# Grove_-_3-Axis_Digital_Accelerometer_1_5.net
KiCad netlist of a schematic drawn in EAGLE
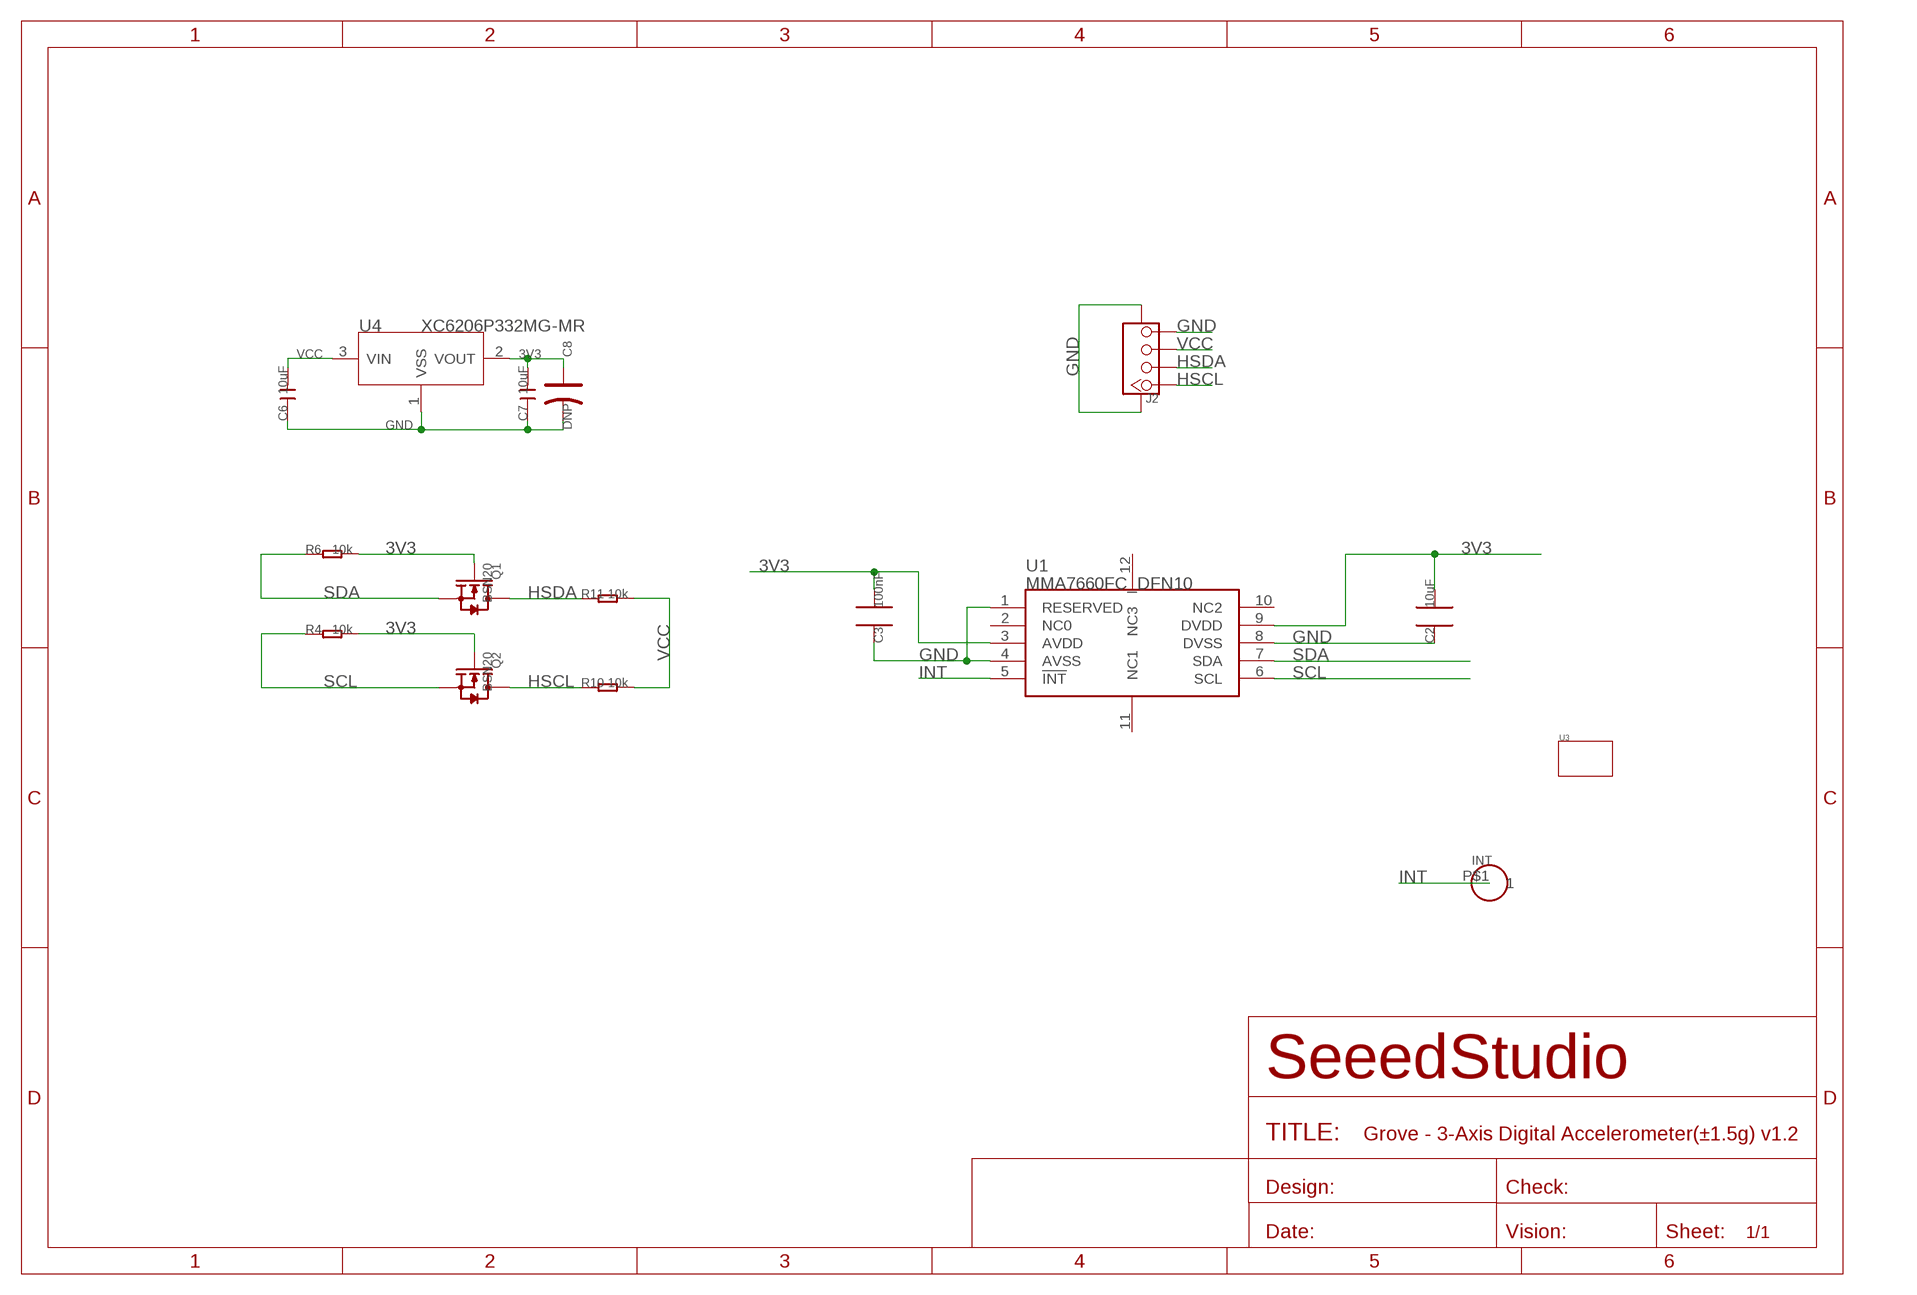
[diagram p0: schematic, sheet 1]

(export (version "E")
  (design (tool "Eeschema 10.0.6"))
  (components
    (comp (ref "C2")
      (value "10uF")
      (footprint "eagle-import:0805_S")
      (libsource (lib "eagle-import") (part "C0805_S"))
    )
    (comp (ref "C3")
      (value "100nF")
      (footprint "eagle-import:0603_S")
      (libsource (lib "eagle-import") (part "C0603_S"))
    )
    (comp (ref "C6")
      (value "10uF")
      (footprint "eagle-import:C0805")
      (libsource (lib "eagle-import") (part "C-0805"))
    )
    (comp (ref "C7")
      (value "10uF")
      (footprint "eagle-import:C0805")
      (libsource (lib "eagle-import") (part "C-0805"))
    )
    (comp (ref "C8")
      (value "DNP")
      (footprint "eagle-import:AVX-A")
      (libsource (lib "eagle-import") (part "CAP-AVX-A"))
    )
    (comp (ref "INT")
      (value "HEADER-1P-35")
      (footprint "eagle-import:1P-65_35MIL")
      (libsource (lib "eagle-import") (part "HEADER-1P-35"))
    )
    (comp (ref "J2")
      (value "TWIG-4P-2.0-SMD-FEMALE-REINFORCE'DD'")
      (footprint "eagle-import:4P-SMD-2.0")
      (libsource (lib "eagle-import") (part "TWIG-4P-2.0-SMD-FEMALE-REINFORCE'DD'"))
    )
    (comp (ref "Q1")
      (value "BSN20")
      (footprint "eagle-import:SOT23")
      (libsource (lib "eagle-import") (part "MOSFET-N'SOT23'"))
    )
    (comp (ref "Q2")
      (value "BSN20")
      (footprint "eagle-import:SOT23")
      (libsource (lib "eagle-import") (part "MOSFET-N'SOT23'"))
    )
    (comp (ref "R4")
      (value "10k")
      (footprint "eagle-import:R0603")
      (libsource (lib "eagle-import") (part "R-0603"))
    )
    (comp (ref "R6")
      (value "10k")
      (footprint "eagle-import:R0603")
      (libsource (lib "eagle-import") (part "R-0603"))
    )
    (comp (ref "R10")
      (value "10k")
      (footprint "eagle-import:R0603")
      (libsource (lib "eagle-import") (part "R-0603"))
    )
    (comp (ref "R11")
      (value "10k")
      (footprint "eagle-import:R0603")
      (libsource (lib "eagle-import") (part "R-0603"))
    )
    (comp (ref "U1")
      (value "MMA7660FC_DFN10")
      (footprint "eagle-import:DFN10")
      (libsource (lib "eagle-import") (part "MMA7660FC_DFN10"))
    )
    (comp (ref "U3")
      (value "TWIG-1U")
      (footprint "eagle-import:1U-DIM-W_-DRILL")
      (libsource (lib "eagle-import") (part "TWIG-1U"))
    )
    (comp (ref "U4")
      (value "XC6206P332MG-MR")
      (footprint "eagle-import:SOT23")
      (libsource (lib "eagle-import") (part "XC6206MR"))
    )
  )
  (nets
    (net (code "1") (name "/3V3") (class "Default")
      (node (ref "C2") (pin "2") (pinfunction "2_2") (pintype "bidirectional"))
      (node (ref "C3") (pin "2") (pinfunction "2_2") (pintype "bidirectional"))
      (node (ref "C7") (pin "2") (pinfunction "2_2") (pintype "passive"))
      (node (ref "C8") (pin "+") (pinfunction "+_+") (pintype "passive"))
      (node (ref "Q1") (pin "1") (pinfunction "G_1") (pintype "passive"))
      (node (ref "Q2") (pin "1") (pinfunction "G_1") (pintype "passive"))
      (node (ref "R4") (pin "2") (pinfunction "2_2") (pintype "passive"))
      (node (ref "R6") (pin "2") (pinfunction "2_2") (pintype "passive"))
      (node (ref "U1") (pin "3") (pinfunction "AVDD_3") (pintype "bidirectional"))
      (node (ref "U1") (pin "9") (pinfunction "DVDD_9") (pintype "bidirectional"))
      (node (ref "U4") (pin "2") (pinfunction "VOUT_2") (pintype "output"))
    )
    (net (code "2") (name "/GND") (class "Default")
      (node (ref "C2") (pin "1") (pinfunction "1_1") (pintype "bidirectional"))
      (node (ref "C3") (pin "1") (pinfunction "1_1") (pintype "bidirectional"))
      (node (ref "C6") (pin "1") (pinfunction "1_1") (pintype "passive"))
      (node (ref "C7") (pin "1") (pinfunction "1_1") (pintype "passive"))
      (node (ref "C8") (pin "-") (pinfunction "-_-") (pintype "passive"))
      (node (ref "J2") (pin "4") (pinfunction "4_4") (pintype "bidirectional"))
      (node (ref "J2") (pin "SS1") (pinfunction "SS1_SS1") (pintype "bidirectional"))
      (node (ref "J2") (pin "SS2") (pinfunction "SS2_SS2") (pintype "bidirectional"))
      (node (ref "U1") (pin "1") (pinfunction "RESERVED_1") (pintype "bidirectional"))
      (node (ref "U1") (pin "4") (pinfunction "AVSS_4") (pintype "bidirectional"))
      (node (ref "U1") (pin "8") (pinfunction "DVSS_8") (pintype "bidirectional"))
      (node (ref "U4") (pin "1") (pinfunction "VSS_1") (pintype "power_in"))
    )
    (net (code "3") (name "/HSCL") (class "Default")
      (node (ref "J2") (pin "1") (pinfunction "1_1") (pintype "bidirectional"))
      (node (ref "Q2") (pin "3") (pinfunction "D_3") (pintype "passive"))
      (node (ref "R10") (pin "1") (pinfunction "1_1") (pintype "passive"))
    )
    (net (code "4") (name "/HSDA") (class "Default")
      (node (ref "J2") (pin "2") (pinfunction "2_2") (pintype "bidirectional"))
      (node (ref "Q1") (pin "3") (pinfunction "D_3") (pintype "passive"))
      (node (ref "R11") (pin "1") (pinfunction "1_1") (pintype "passive"))
    )
    (net (code "5") (name "/INT") (class "Default")
      (node (ref "INT") (pin "P$1") (pinfunction "1_P$1") (pintype "bidirectional"))
      (node (ref "U1") (pin "5") (pinfunction "~{INT}_5") (pintype "bidirectional"))
    )
    (net (code "6") (name "/SCL") (class "Default")
      (node (ref "Q2") (pin "2") (pinfunction "S_2") (pintype "passive"))
      (node (ref "R4") (pin "1") (pinfunction "1_1") (pintype "passive"))
      (node (ref "U1") (pin "6") (pinfunction "SCL_6") (pintype "bidirectional"))
    )
    (net (code "7") (name "/SDA") (class "Default")
      (node (ref "Q1") (pin "2") (pinfunction "S_2") (pintype "passive"))
      (node (ref "R6") (pin "1") (pinfunction "1_1") (pintype "passive"))
      (node (ref "U1") (pin "7") (pinfunction "SDA_7") (pintype "bidirectional"))
    )
    (net (code "8") (name "/VCC") (class "Default")
      (node (ref "C6") (pin "2") (pinfunction "2_2") (pintype "passive"))
      (node (ref "J2") (pin "3") (pinfunction "3_3") (pintype "bidirectional"))
      (node (ref "R10") (pin "2") (pinfunction "2_2") (pintype "passive"))
      (node (ref "R11") (pin "2") (pinfunction "2_2") (pintype "passive"))
      (node (ref "U4") (pin "3") (pinfunction "VIN_3") (pintype "input"))
    )
    (net (code "9") (name "unconnected-(U1-NC0-Pad2)") (class "Default")
      (node (ref "U1") (pin "2") (pinfunction "NC0_2") (pintype "bidirectional"))
    )
    (net (code "10") (name "unconnected-(U1-NC1-Pad11)") (class "Default")
      (node (ref "U1") (pin "11") (pinfunction "NC1_11") (pintype "bidirectional"))
    )
    (net (code "11") (name "unconnected-(U1-NC2-Pad10)") (class "Default")
      (node (ref "U1") (pin "10") (pinfunction "NC2_10") (pintype "bidirectional"))
    )
    (net (code "12") (name "unconnected-(U1-NC3-Pad12)") (class "Default")
      (node (ref "U1") (pin "12") (pinfunction "NC3_12") (pintype "bidirectional"))
    )
  )
)
